# Interrupter.net
KiCad netlist of a schematic drawn in Altium Designer
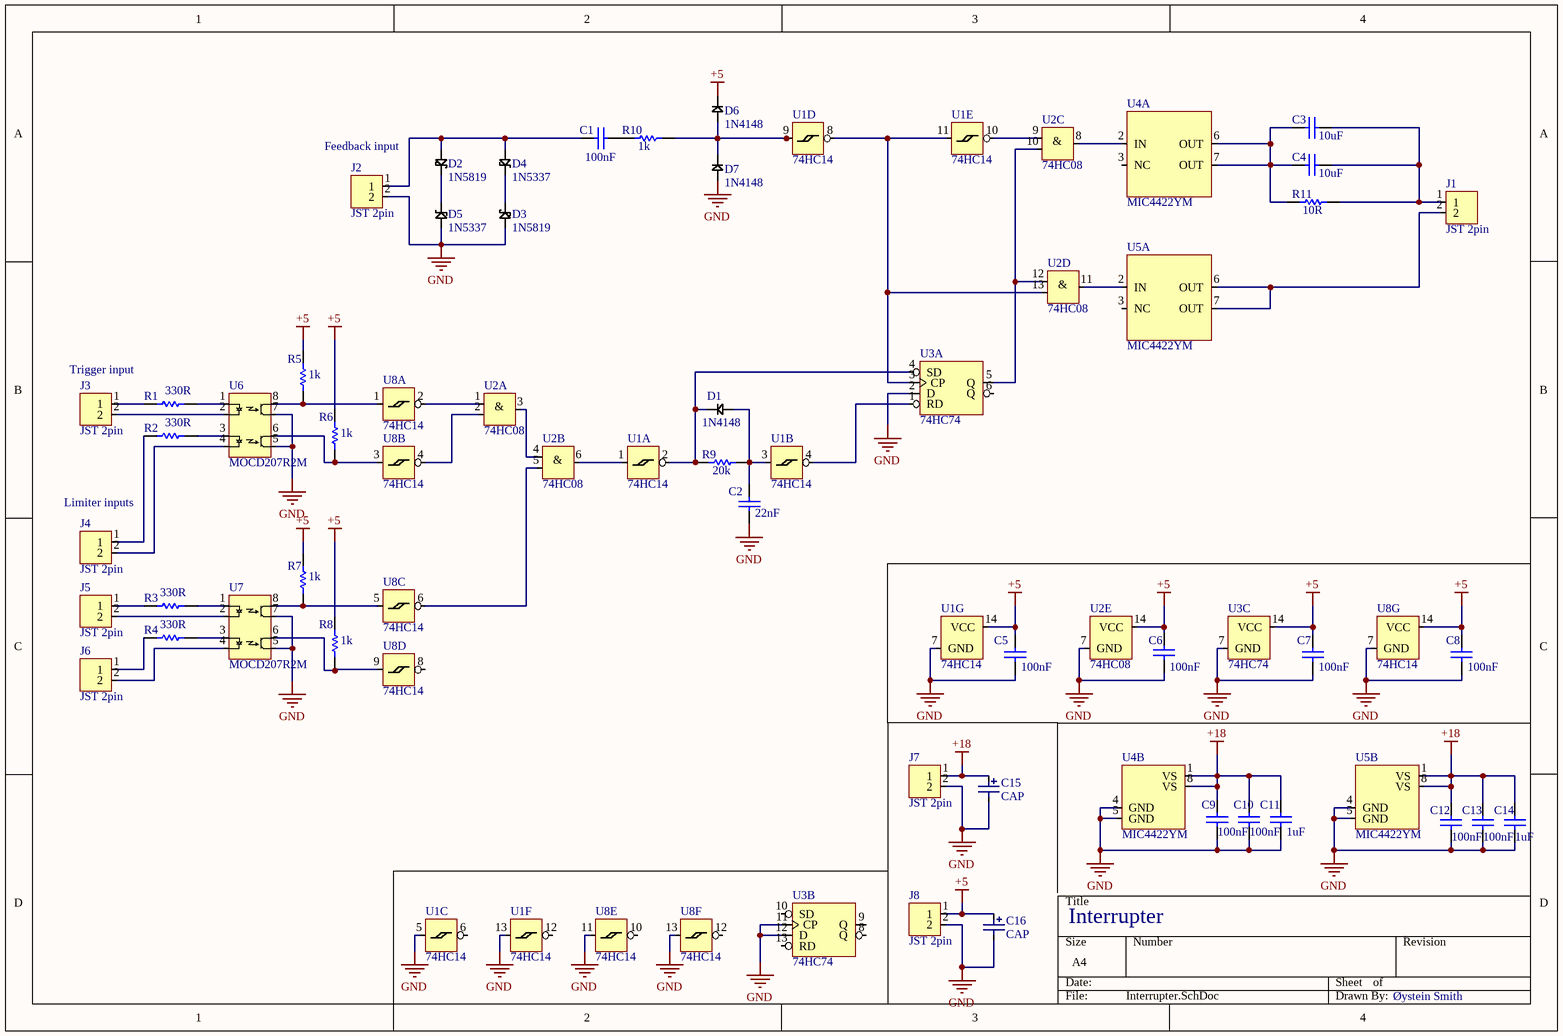
[diagram p0: Interrupter.SchDoc]

(export (version "E")
  (design (tool "Eeschema 10.0.6"))
  (components
    (comp (ref "C1")
      (value "100nF")
      (footprint "CAPC0805(2012)145_L")
      (description "CAP 100nF 25V ±10% 0805 (2012 Metric) Thickness 1.45mm SMD")
      (fields (field (name "TOLERANCE") "±10%") (field (name "Comment") "CAP 100nF 25V 0805(2012)"))
      (libsource (lib "Altium Content Vault") (part "CMP-1036-04410-1"))
    )
    (comp (ref "C2")
      (value "22nF")
      (footprint "CAPC0805(2012)145_L")
      (description "CAP 22nF 25V ±5% 0805 (2012 Metric) Thickness 1.45mm SMD")
      (fields (field (name "TOLERANCE") "±5%") (field (name "Comment") "CAP 22nF 25V 0805(2012)"))
      (libsource (lib "Altium Content Vault") (part "CMP-1036-04050-1"))
    )
    (comp (ref "C3")
      (value "10uF")
      (footprint "CAPC1206(3216)190_L")
      (description "CAP 10uF 25V ±10% 1206 (3216 Metric) Thickness 1.9mm SMD")
      (fields (field (name "TOLERANCE") "±10%") (field (name "Comment") "CAP 10uF 25V 1206(3216)"))
      (libsource (lib "Altium Content Vault") (part "CMP-1037-04979-1"))
    )
    (comp (ref "C4")
      (value "10uF")
      (footprint "CAPC1206(3216)190_L")
      (description "CAP 10uF 25V ±10% 1206 (3216 Metric) Thickness 1.9mm SMD")
      (fields (field (name "TOLERANCE") "±10%") (field (name "Comment") "CAP 10uF 25V 1206(3216)"))
      (libsource (lib "Altium Content Vault") (part "CMP-1037-04979-1"))
    )
    (comp (ref "C5")
      (value "100nF")
      (footprint "CAPC0805(2012)145_M")
      (description "CAP 100nF 25V ±5% 0805 (2012 Metric) Thickness 1.45mm SMD")
      (fields (field (name "TOLERANCE") "±5%") (field (name "Comment") "CAP 100nF 25V 0805(2012)"))
      (libsource (lib "Altium Content Vault") (part "CMP-1036-04408-1"))
    )
    (comp (ref "C6")
      (value "100nF")
      (footprint "CAPC0805(2012)145_M")
      (description "CAP 100nF 25V ±5% 0805 (2012 Metric) Thickness 1.45mm SMD")
      (fields (field (name "TOLERANCE") "±5%") (field (name "Comment") "CAP 100nF 25V 0805(2012)"))
      (libsource (lib "Altium Content Vault") (part "CMP-1036-04408-1"))
    )
    (comp (ref "C7")
      (value "100nF")
      (footprint "CAPC0805(2012)145_M")
      (description "CAP 100nF 25V ±5% 0805 (2012 Metric) Thickness 1.45mm SMD")
      (fields (field (name "TOLERANCE") "±5%") (field (name "Comment") "CAP 100nF 25V 0805(2012)"))
      (libsource (lib "Altium Content Vault") (part "CMP-1036-04408-1"))
    )
    (comp (ref "C8")
      (value "100nF")
      (footprint "CAPC0805(2012)145_M")
      (description "CAP 100nF 25V ±5% 0805 (2012 Metric) Thickness 1.45mm SMD")
      (fields (field (name "TOLERANCE") "±5%") (field (name "Comment") "CAP 100nF 25V 0805(2012)"))
      (libsource (lib "Altium Content Vault") (part "CMP-1036-04408-1"))
    )
    (comp (ref "C9")
      (value "100nF")
      (footprint "CAPC0805(2012)145_M")
      (description "CAP 100nF 25V ±5% 0805 (2012 Metric) Thickness 1.45mm SMD")
      (fields (field (name "TOLERANCE") "±5%") (field (name "Comment") "CAP 100nF 25V 0805(2012)"))
      (libsource (lib "Altium Content Vault") (part "CMP-1036-04408-1"))
    )
    (comp (ref "C10")
      (value "100nF")
      (footprint "CAPC0805(2012)145_M")
      (description "CAP 100nF 25V ±5% 0805 (2012 Metric) Thickness 1.45mm SMD")
      (fields (field (name "TOLERANCE") "±5%") (field (name "Comment") "CAP 100nF 25V 0805(2012)"))
      (libsource (lib "Altium Content Vault") (part "CMP-1036-04408-1"))
    )
    (comp (ref "C11")
      (value "1uF")
      (footprint "CAPC0805(2012)145_N")
      (description "CAP 1uF 25V ±5% 0805 (2012 Metric) Thickness 1.45mm SMD")
      (fields (field (name "TOLERANCE") "±5%") (field (name "Comment") "CAP 1uF 25V 0805(2012)"))
      (libsource (lib "Altium Content Vault") (part "CMP-1036-04752-1"))
    )
    (comp (ref "C12")
      (value "100nF")
      (footprint "CAPC0805(2012)145_M")
      (description "CAP 100nF 25V ±5% 0805 (2012 Metric) Thickness 1.45mm SMD")
      (fields (field (name "TOLERANCE") "±5%") (field (name "Comment") "CAP 100nF 25V 0805(2012)"))
      (libsource (lib "Altium Content Vault") (part "CMP-1036-04408-1"))
    )
    (comp (ref "C13")
      (value "100nF")
      (footprint "CAPC0805(2012)145_M")
      (description "CAP 100nF 25V ±5% 0805 (2012 Metric) Thickness 1.45mm SMD")
      (fields (field (name "TOLERANCE") "±5%") (field (name "Comment") "CAP 100nF 25V 0805(2012)"))
      (libsource (lib "Altium Content Vault") (part "CMP-1036-04408-1"))
    )
    (comp (ref "C14")
      (value "1uF")
      (footprint "CAPC0805(2012)145_N")
      (description "CAP 1uF 25V ±5% 0805 (2012 Metric) Thickness 1.45mm SMD")
      (fields (field (name "TOLERANCE") "±5%") (field (name "Comment") "CAP 1uF 25V 0805(2012)"))
      (libsource (lib "Altium Content Vault") (part "CMP-1036-04752-1"))
    )
    (comp (ref "C15") (value "CAP") (footprint "CAP 2.5mm") (libsource (lib "Schlib1") (part "CAP")))
    (comp (ref "C16") (value "CAP") (footprint "CAP 2.5mm") (libsource (lib "Schlib1") (part "CAP")))
    (comp (ref "D1") (value "1N4148") (footprint "1N4148") (libsource (lib "Schlib1") (part "1N4148")))
    (comp (ref "D2") (value "1N5819") (footprint "1N5819") (libsource (lib "Schlib1") (part "1N5819")))
    (comp (ref "D3") (value "1N5819") (footprint "1N5819") (libsource (lib "Schlib1") (part "1N5819")))
    (comp (ref "D4") (value "1N5337") (footprint "1N5337") (libsource (lib "Schlib1") (part "1N5337")))
    (comp (ref "D5") (value "1N5337") (footprint "1N5337") (libsource (lib "Schlib1") (part "1N5337")))
    (comp (ref "D6") (value "1N4148") (footprint "1N4148") (libsource (lib "Schlib1") (part "1N4148")))
    (comp (ref "D7") (value "1N4148") (footprint "1N4148") (libsource (lib "Schlib1") (part "1N4148")))
    (comp (ref "J1") (value "JST 2pin") (footprint "JST 2pin") (libsource (lib "") (part "JST 2pin_1")))
    (comp (ref "J2") (value "JST 2pin") (footprint "JST 2pin") (libsource (lib "Schlib1") (part "JST 2pin")))
    (comp (ref "J3") (value "JST 2pin") (footprint "JST 2pin") (libsource (lib "Schlib1") (part "JST 2pin")))
    (comp (ref "J4") (value "JST 2pin") (footprint "JST 2pin") (libsource (lib "Schlib1") (part "JST 2pin")))
    (comp (ref "J5") (value "JST 2pin") (footprint "JST 2pin") (libsource (lib "Schlib1") (part "JST 2pin")))
    (comp (ref "J6") (value "JST 2pin") (footprint "JST 2pin") (libsource (lib "Schlib1") (part "JST 2pin")))
    (comp (ref "J7") (value "JST 2pin") (footprint "JST 2pin") (libsource (lib "Schlib1") (part "JST 2pin")))
    (comp (ref "J8") (value "JST 2pin") (footprint "JST 2pin") (libsource (lib "Schlib1") (part "JST 2pin")))
    (comp (ref "R1")
      (value "330R")
      (footprint "RESC0805(2012)_L")
      (description "330R 0.125W 5% 0805 (2012 Metric)  SMD")
      (fields (field (name "TOLERANCE") "5 %") (field (name "POWER") "0.125 W"))
      (libsource (lib "Altium Content Vault") (part "CMP-1013-00062-1"))
    )
    (comp (ref "R2")
      (value "330R")
      (footprint "RESC0805(2012)_L")
      (description "330R 0.125W 5% 0805 (2012 Metric)  SMD")
      (fields (field (name "TOLERANCE") "5 %") (field (name "POWER") "0.125 W"))
      (libsource (lib "Altium Content Vault") (part "CMP-1013-00062-1"))
    )
    (comp (ref "R3")
      (value "330R")
      (footprint "RESC0805(2012)_L")
      (description "330R 0.125W 5% 0805 (2012 Metric)  SMD")
      (fields (field (name "TOLERANCE") "5 %") (field (name "POWER") "0.125 W"))
      (libsource (lib "Altium Content Vault") (part "CMP-1013-00062-1"))
    )
    (comp (ref "R4")
      (value "330R")
      (footprint "RESC0805(2012)_L")
      (description "330R 0.125W 5% 0805 (2012 Metric)  SMD")
      (fields (field (name "TOLERANCE") "5 %") (field (name "POWER") "0.125 W"))
      (libsource (lib "Altium Content Vault") (part "CMP-1013-00062-1"))
    )
    (comp (ref "R5")
      (value "1k")
      (footprint "RESC0805(2012)_N")
      (description "1K 0.125W 5% 0805 (2012 Metric)  SMD")
      (fields (field (name "POWER") "0.125 W") (field (name "TOLERANCE") "5 %"))
      (libsource (lib "Altium Content Vault") (part "CMP-1013-00074-1"))
    )
    (comp (ref "R6")
      (value "1k")
      (footprint "RESC0805(2012)_N")
      (description "1K 0.125W 5% 0805 (2012 Metric)  SMD")
      (fields (field (name "POWER") "0.125 W") (field (name "TOLERANCE") "5 %"))
      (libsource (lib "Altium Content Vault") (part "CMP-1013-00074-1"))
    )
    (comp (ref "R7")
      (value "1k")
      (footprint "RESC0805(2012)_N")
      (description "1K 0.125W 5% 0805 (2012 Metric)  SMD")
      (fields (field (name "POWER") "0.125 W") (field (name "TOLERANCE") "5 %"))
      (libsource (lib "Altium Content Vault") (part "CMP-1013-00074-1"))
    )
    (comp (ref "R8")
      (value "1k")
      (footprint "RESC0805(2012)_N")
      (description "1K 0.125W 5% 0805 (2012 Metric)  SMD")
      (fields (field (name "POWER") "0.125 W") (field (name "TOLERANCE") "5 %"))
      (libsource (lib "Altium Content Vault") (part "CMP-1013-00074-1"))
    )
    (comp (ref "R9")
      (value "20k")
      (footprint "RESC0805(2012)_N")
      (description "20K 0.125W 1% 0805 (2012 Metric)  SMD")
      (fields (field (name "POWER") "0.125 W") (field (name "TOLERANCE") "1 %"))
      (libsource (lib "Altium Content Vault") (part "CMP-1013-00655-1"))
    )
    (comp (ref "R10")
      (value "1k")
      (footprint "RESC0805(2012)_M")
      (description "1K 0.125W 1% 0805 (2012 Metric)  SMD")
      (fields (field (name "TOLERANCE") "1 %") (field (name "POWER") "0.125 W"))
      (libsource (lib "Altium Content Vault") (part "CMP-1013-00510-1"))
    )
    (comp (ref "R11")
      (value "10R")
      (footprint "RESC0805(2012)_L")
      (description "10R 0.125W 5% 0805 (2012 Metric)  SMD")
      (fields (field (name "POWER") "0.125 W") (field (name "TOLERANCE") "5 %"))
      (libsource (lib "Altium Content Vault") (part "CMP-1013-00026-1"))
    )
    (comp (ref "U1") (value "74HC14") (footprint "SOP14") (libsource (lib "Schlib1") (part "74HC14")))
    (comp (ref "U2") (value "74HC08") (footprint "SOP14") (libsource (lib "Schlib1") (part "74HC08")))
    (comp (ref "U3") (value "74HC74") (footprint "SOP14") (libsource (lib "Schlib1") (part "74HC74")))
    (comp (ref "U4") (value "MIC4422YM") (footprint "SOP8") (libsource (lib "Schlib1") (part "MIC4422YM")))
    (comp (ref "U5") (value "MIC4422YM") (footprint "SOP8") (libsource (lib "Schlib1") (part "MIC4422YM")))
    (comp (ref "U6") (value "MOCD207R2M") (footprint "SOP8") (libsource (lib "Schlib1") (part "MOCD207R2M")))
    (comp (ref "U7") (value "MOCD207R2M") (footprint "SOP8") (libsource (lib "Schlib1") (part "MOCD207R2M")))
    (comp (ref "U8") (value "74HC14") (footprint "SOP14") (libsource (lib "Schlib1") (part "74HC14")))
  )
  (nets
    (net (code "1") (name "+5") (class "Default")
      (node (ref "C16") (pin "2") (pinfunction "2_2") (pintype "passive"))
      (node (ref "C5") (pin "2") (pinfunction "2_2") (pintype "passive"))
      (node (ref "C6") (pin "2") (pinfunction "2_2") (pintype "passive"))
      (node (ref "C7") (pin "2") (pinfunction "2_2") (pintype "passive"))
      (node (ref "C8") (pin "2") (pinfunction "2_2") (pintype "passive"))
      (node (ref "D6") (pin "K") (pinfunction "K_K") (pintype "passive"))
      (node (ref "J8") (pin "1") (pinfunction "1_1") (pintype "passive"))
      (node (ref "R5") (pin "2") (pinfunction "2_2") (pintype "passive"))
      (node (ref "R6") (pin "2") (pinfunction "2_2") (pintype "passive"))
      (node (ref "R7") (pin "2") (pinfunction "2_2") (pintype "passive"))
      (node (ref "R8") (pin "2") (pinfunction "2_2") (pintype "passive"))
      (node (ref "U1") (pin "14") (pinfunction "VCC_14") (pintype "passive"))
      (node (ref "U2") (pin "14") (pinfunction "VCC_14") (pintype "passive"))
      (node (ref "U3") (pin "14") (pinfunction "VCC_14") (pintype "passive"))
      (node (ref "U8") (pin "14") (pinfunction "VCC_14") (pintype "passive"))
    )
    (net (code "2") (name "+18") (class "Default")
      (node (ref "C10") (pin "2") (pinfunction "2_2") (pintype "passive"))
      (node (ref "C11") (pin "2") (pinfunction "2_2") (pintype "passive"))
      (node (ref "C12") (pin "2") (pinfunction "2_2") (pintype "passive"))
      (node (ref "C13") (pin "2") (pinfunction "2_2") (pintype "passive"))
      (node (ref "C14") (pin "2") (pinfunction "2_2") (pintype "passive"))
      (node (ref "C15") (pin "2") (pinfunction "2_2") (pintype "passive"))
      (node (ref "C9") (pin "2") (pinfunction "2_2") (pintype "passive"))
      (node (ref "J7") (pin "1") (pinfunction "1_1") (pintype "passive"))
      (node (ref "U4") (pin "1") (pinfunction "VS_1") (pintype "passive"))
      (node (ref "U4") (pin "8") (pinfunction "VS_8") (pintype "passive"))
      (node (ref "U5") (pin "1") (pinfunction "VS_1") (pintype "passive"))
      (node (ref "U5") (pin "8") (pinfunction "VS_8") (pintype "passive"))
    )
    (net (code "3") (name "GND") (class "Default")
      (node (ref "C10") (pin "1") (pinfunction "1_1") (pintype "passive"))
      (node (ref "C11") (pin "1") (pinfunction "1_1") (pintype "passive"))
      (node (ref "C12") (pin "1") (pinfunction "1_1") (pintype "passive"))
      (node (ref "C13") (pin "1") (pinfunction "1_1") (pintype "passive"))
      (node (ref "C14") (pin "1") (pinfunction "1_1") (pintype "passive"))
      (node (ref "C15") (pin "1") (pinfunction "1_1") (pintype "passive"))
      (node (ref "C16") (pin "1") (pinfunction "1_1") (pintype "passive"))
      (node (ref "C2") (pin "1") (pinfunction "1_1") (pintype "passive"))
      (node (ref "C5") (pin "1") (pinfunction "1_1") (pintype "passive"))
      (node (ref "C6") (pin "1") (pinfunction "1_1") (pintype "passive"))
      (node (ref "C7") (pin "1") (pinfunction "1_1") (pintype "passive"))
      (node (ref "C8") (pin "1") (pinfunction "1_1") (pintype "passive"))
      (node (ref "C9") (pin "1") (pinfunction "1_1") (pintype "passive"))
      (node (ref "D3") (pin "A") (pinfunction "A_A") (pintype "passive"))
      (node (ref "D5") (pin "A") (pinfunction "A_A") (pintype "passive"))
      (node (ref "D7") (pin "A") (pinfunction "A_A") (pintype "passive"))
      (node (ref "J2") (pin "2") (pinfunction "2_2") (pintype "passive"))
      (node (ref "J7") (pin "2") (pinfunction "2_2") (pintype "passive"))
      (node (ref "J8") (pin "2") (pinfunction "2_2") (pintype "passive"))
      (node (ref "U1") (pin "13") (pinfunction "13_13") (pintype "passive"))
      (node (ref "U1") (pin "5") (pinfunction "5_5") (pintype "passive"))
      (node (ref "U1") (pin "7") (pinfunction "GND_7") (pintype "passive"))
      (node (ref "U2") (pin "7") (pinfunction "GND_7") (pintype "passive"))
      (node (ref "U3") (pin "11") (pinfunction "CP_11") (pintype "passive"))
      (node (ref "U3") (pin "12") (pinfunction "D_12") (pintype "passive"))
      (node (ref "U3") (pin "2") (pinfunction "D_2") (pintype "passive"))
      (node (ref "U3") (pin "7") (pinfunction "GND_7") (pintype "passive"))
      (node (ref "U4") (pin "4") (pinfunction "GND_4") (pintype "passive"))
      (node (ref "U4") (pin "5") (pinfunction "GND_5") (pintype "passive"))
      (node (ref "U5") (pin "4") (pinfunction "GND_4") (pintype "passive"))
      (node (ref "U5") (pin "5") (pinfunction "GND_5") (pintype "passive"))
      (node (ref "U6") (pin "5") (pinfunction "5_5") (pintype "passive"))
      (node (ref "U6") (pin "7") (pinfunction "7_7") (pintype "passive"))
      (node (ref "U7") (pin "5") (pinfunction "5_5") (pintype "passive"))
      (node (ref "U7") (pin "7") (pinfunction "7_7") (pintype "passive"))
      (node (ref "U8") (pin "11") (pinfunction "11_11") (pintype "passive"))
      (node (ref "U8") (pin "13") (pinfunction "13_13") (pintype "passive"))
      (node (ref "U8") (pin "7") (pinfunction "GND_7") (pintype "passive"))
    )
    (net (code "4") (name "Net-(C1-Pad1)") (class "Default")
      (node (ref "C1") (pin "1") (pinfunction "1_1") (pintype "passive"))
      (node (ref "D2") (pin "A") (pinfunction "A_A") (pintype "passive"))
      (node (ref "D4") (pin "A") (pinfunction "A_A") (pintype "passive"))
      (node (ref "J2") (pin "1") (pinfunction "1_1") (pintype "passive"))
    )
    (net (code "5") (name "Net-(C1-Pad2)") (class "Default")
      (node (ref "C1") (pin "2") (pinfunction "2_2") (pintype "passive"))
      (node (ref "R10") (pin "1") (pinfunction "1_1") (pintype "passive"))
    )
    (net (code "6") (name "Net-(C2-Pad2)") (class "Default")
      (node (ref "C2") (pin "2") (pinfunction "2_2") (pintype "passive"))
      (node (ref "D1") (pin "A") (pinfunction "A_A") (pintype "passive"))
      (node (ref "R9") (pin "2") (pinfunction "2_2") (pintype "passive"))
      (node (ref "U1") (pin "3") (pinfunction "3_3") (pintype "passive"))
    )
    (net (code "7") (name "Net-(C3-Pad1)") (class "Default")
      (node (ref "C3") (pin "1") (pinfunction "1_1") (pintype "passive"))
      (node (ref "C4") (pin "1") (pinfunction "1_1") (pintype "passive"))
      (node (ref "R11") (pin "1") (pinfunction "1_1") (pintype "passive"))
      (node (ref "U4") (pin "6") (pinfunction "OUT_6") (pintype "passive"))
      (node (ref "U4") (pin "7") (pinfunction "OUT_7") (pintype "passive"))
    )
    (net (code "8") (name "Net-(C3-Pad2)") (class "Default")
      (node (ref "C3") (pin "2") (pinfunction "2_2") (pintype "passive"))
      (node (ref "C4") (pin "2") (pinfunction "2_2") (pintype "passive"))
      (node (ref "J1") (pin "1") (pinfunction "1_1") (pintype "passive"))
      (node (ref "R11") (pin "2") (pinfunction "2_2") (pintype "passive"))
    )
    (net (code "9") (name "Net-(D2-PadK)") (class "Default")
      (node (ref "D2") (pin "K") (pinfunction "K_K") (pintype "passive"))
      (node (ref "D5") (pin "K") (pinfunction "K_K") (pintype "passive"))
    )
    (net (code "10") (name "Net-(D3-PadK)") (class "Default")
      (node (ref "D3") (pin "K") (pinfunction "K_K") (pintype "passive"))
      (node (ref "D4") (pin "K") (pinfunction "K_K") (pintype "passive"))
    )
    (net (code "11") (name "Net-(D6-PadA)") (class "Default")
      (node (ref "D6") (pin "A") (pinfunction "A_A") (pintype "passive"))
      (node (ref "D7") (pin "K") (pinfunction "K_K") (pintype "passive"))
      (node (ref "R10") (pin "2") (pinfunction "2_2") (pintype "passive"))
      (node (ref "U1") (pin "9") (pinfunction "9_9") (pintype "passive"))
    )
    (net (code "12") (name "Net-(J1-Pad2)") (class "Default")
      (node (ref "J1") (pin "2") (pinfunction "2_2") (pintype "passive"))
      (node (ref "U5") (pin "6") (pinfunction "OUT_6") (pintype "passive"))
      (node (ref "U5") (pin "7") (pinfunction "OUT_7") (pintype "passive"))
    )
    (net (code "13") (name "Net-(J3-Pad1)") (class "Default")
      (node (ref "J3") (pin "1") (pinfunction "1_1") (pintype "passive"))
      (node (ref "R1") (pin "2") (pinfunction "2_2") (pintype "passive"))
    )
    (net (code "14") (name "Net-(J3-Pad2)") (class "Default")
      (node (ref "J3") (pin "2") (pinfunction "2_2") (pintype "passive"))
      (node (ref "U6") (pin "2") (pinfunction "2_2") (pintype "passive"))
    )
    (net (code "15") (name "Net-(J4-Pad1)") (class "Default")
      (node (ref "J4") (pin "1") (pinfunction "1_1") (pintype "passive"))
      (node (ref "R2") (pin "2") (pinfunction "2_2") (pintype "passive"))
    )
    (net (code "16") (name "Net-(J4-Pad2)") (class "Default")
      (node (ref "J4") (pin "2") (pinfunction "2_2") (pintype "passive"))
      (node (ref "U6") (pin "4") (pinfunction "4_4") (pintype "passive"))
    )
    (net (code "17") (name "Net-(J5-Pad1)") (class "Default")
      (node (ref "J5") (pin "1") (pinfunction "1_1") (pintype "passive"))
      (node (ref "R3") (pin "2") (pinfunction "2_2") (pintype "passive"))
    )
    (net (code "18") (name "Net-(J5-Pad2)") (class "Default")
      (node (ref "J5") (pin "2") (pinfunction "2_2") (pintype "passive"))
      (node (ref "U7") (pin "2") (pinfunction "2_2") (pintype "passive"))
    )
    (net (code "19") (name "Net-(J6-Pad1)") (class "Default")
      (node (ref "J6") (pin "1") (pinfunction "1_1") (pintype "passive"))
      (node (ref "R4") (pin "2") (pinfunction "2_2") (pintype "passive"))
    )
    (net (code "20") (name "Net-(J6-Pad2)") (class "Default")
      (node (ref "J6") (pin "2") (pinfunction "2_2") (pintype "passive"))
      (node (ref "U7") (pin "4") (pinfunction "4_4") (pintype "passive"))
    )
    (net (code "21") (name "Net-(R1-Pad1)") (class "Default")
      (node (ref "R1") (pin "1") (pinfunction "1_1") (pintype "passive"))
      (node (ref "U6") (pin "1") (pinfunction "1_1") (pintype "passive"))
    )
    (net (code "22") (name "Net-(R2-Pad1)") (class "Default")
      (node (ref "R2") (pin "1") (pinfunction "1_1") (pintype "passive"))
      (node (ref "U6") (pin "3") (pinfunction "3_3") (pintype "passive"))
    )
    (net (code "23") (name "Net-(R3-Pad1)") (class "Default")
      (node (ref "R3") (pin "1") (pinfunction "1_1") (pintype "passive"))
      (node (ref "U7") (pin "1") (pinfunction "1_1") (pintype "passive"))
    )
    (net (code "24") (name "Net-(R4-Pad1)") (class "Default")
      (node (ref "R4") (pin "1") (pinfunction "1_1") (pintype "passive"))
      (node (ref "U7") (pin "3") (pinfunction "3_3") (pintype "passive"))
    )
    (net (code "25") (name "Net-(R5-Pad1)") (class "Default")
      (node (ref "R5") (pin "1") (pinfunction "1_1") (pintype "passive"))
      (node (ref "U6") (pin "8") (pinfunction "8_8") (pintype "passive"))
      (node (ref "U8") (pin "1") (pinfunction "1_1") (pintype "passive"))
    )
    (net (code "26") (name "Net-(R6-Pad1)") (class "Default")
      (node (ref "R6") (pin "1") (pinfunction "1_1") (pintype "passive"))
      (node (ref "U6") (pin "6") (pinfunction "6_6") (pintype "passive"))
      (node (ref "U8") (pin "3") (pinfunction "3_3") (pintype "passive"))
    )
    (net (code "27") (name "Net-(R7-Pad1)") (class "Default")
      (node (ref "R7") (pin "1") (pinfunction "1_1") (pintype "passive"))
      (node (ref "U7") (pin "8") (pinfunction "8_8") (pintype "passive"))
      (node (ref "U8") (pin "5") (pinfunction "5_5") (pintype "passive"))
    )
    (net (code "28") (name "Net-(R8-Pad1)") (class "Default")
      (node (ref "R8") (pin "1") (pinfunction "1_1") (pintype "passive"))
      (node (ref "U7") (pin "6") (pinfunction "6_6") (pintype "passive"))
      (node (ref "U8") (pin "9") (pinfunction "9_9") (pintype "passive"))
    )
    (net (code "29") (name "Net-(U1-Pad1)") (class "Default")
      (node (ref "U1") (pin "1") (pinfunction "1_1") (pintype "passive"))
      (node (ref "U2") (pin "6") (pinfunction "6_6") (pintype "passive"))
    )
    (net (code "30") (name "Net-(U1-Pad10)") (class "Default")
      (node (ref "U1") (pin "10") (pinfunction "10_10") (pintype "passive"))
      (node (ref "U2") (pin "9") (pinfunction "9_9") (pintype "passive"))
    )
    (net (code "31") (name "Net-(U2-Pad1)") (class "Default")
      (node (ref "U2") (pin "1") (pinfunction "1_1") (pintype "passive"))
      (node (ref "U8") (pin "2") (pinfunction "2_2") (pintype "passive"))
    )
    (net (code "32") (name "Net-(U2-Pad2)") (class "Default")
      (node (ref "U2") (pin "2") (pinfunction "2_2") (pintype "passive"))
      (node (ref "U8") (pin "4") (pinfunction "4_4") (pintype "passive"))
    )
    (net (code "33") (name "Net-(U2-Pad3)") (class "Default")
      (node (ref "U2") (pin "3") (pinfunction "3_3") (pintype "passive"))
      (node (ref "U2") (pin "4") (pinfunction "4_4") (pintype "passive"))
    )
    (net (code "34") (name "Net-(U2-Pad5)") (class "Default")
      (node (ref "U2") (pin "5") (pinfunction "5_5") (pintype "passive"))
      (node (ref "U8") (pin "6") (pinfunction "6_6") (pintype "passive"))
    )
    (net (code "35") (name "Net-(U2-Pad10)") (class "Default")
      (node (ref "U2") (pin "10") (pinfunction "10_10") (pintype "passive"))
      (node (ref "U2") (pin "12") (pinfunction "12_12") (pintype "passive"))
      (node (ref "U3") (pin "5") (pinfunction "Q_5") (pintype "passive"))
    )
    (net (code "36") (name "Net-(U3A-CP)") (class "Default")
      (node (ref "U1") (pin "11") (pinfunction "11_11") (pintype "passive"))
      (node (ref "U1") (pin "8") (pinfunction "8_8") (pintype "passive"))
      (node (ref "U2") (pin "13") (pinfunction "13_13") (pintype "passive"))
      (node (ref "U3") (pin "3") (pinfunction "CP_3") (pintype "passive"))
    )
    (net (code "37") (name "Net-(U3A-RD)") (class "Default")
      (node (ref "U1") (pin "4") (pinfunction "4_4") (pintype "passive"))
      (node (ref "U3") (pin "1") (pinfunction "RD_1") (pintype "passive"))
    )
    (net (code "38") (name "Net-(U3A-SD)") (class "Default")
      (node (ref "D1") (pin "K") (pinfunction "K_K") (pintype "passive"))
      (node (ref "R9") (pin "1") (pinfunction "1_1") (pintype "passive"))
      (node (ref "U1") (pin "2") (pinfunction "2_2") (pintype "passive"))
      (node (ref "U3") (pin "4") (pinfunction "SD_4") (pintype "passive"))
    )
    (net (code "39") (name "Net-(U4A-IN)") (class "Default")
      (node (ref "U2") (pin "8") (pinfunction "8_8") (pintype "passive"))
      (node (ref "U4") (pin "2") (pinfunction "IN_2") (pintype "passive"))
    )
    (net (code "40") (name "Net-(U5A-IN)") (class "Default")
      (node (ref "U2") (pin "11") (pinfunction "11_11") (pintype "passive"))
      (node (ref "U5") (pin "2") (pinfunction "IN_2") (pintype "passive"))
    )
    (net (code "41") (name "unconnected-(U1-Pad6)") (class "Default")
      (node (ref "U1") (pin "6") (pinfunction "6_6") (pintype "passive"))
    )
    (net (code "42") (name "unconnected-(U1-Pad12)") (class "Default")
      (node (ref "U1") (pin "12") (pinfunction "12_12") (pintype "passive"))
    )
    (net (code "43") (name "unconnected-(U3A-Q-Pad6)") (class "Default")
      (node (ref "U3") (pin "6") (pinfunction "Q_6") (pintype "passive"))
    )
    (net (code "44") (name "unconnected-(U3B-Q-Pad8)") (class "Default")
      (node (ref "U3") (pin "8") (pinfunction "Q_8") (pintype "passive"))
    )
    (net (code "45") (name "unconnected-(U3B-Q-Pad9)") (class "Default")
      (node (ref "U3") (pin "9") (pinfunction "Q_9") (pintype "passive"))
    )
    (net (code "46") (name "unconnected-(U3B-RD-Pad13)") (class "Default")
      (node (ref "U3") (pin "13") (pinfunction "RD_13") (pintype "passive"))
    )
    (net (code "47") (name "unconnected-(U3B-SD-Pad10)") (class "Default")
      (node (ref "U3") (pin "10") (pinfunction "SD_10") (pintype "passive"))
    )
    (net (code "48") (name "unconnected-(U4A-NC-Pad3)") (class "Default")
      (node (ref "U4") (pin "3") (pinfunction "NC_3") (pintype "passive"))
    )
    (net (code "49") (name "unconnected-(U5A-NC-Pad3)") (class "Default")
      (node (ref "U5") (pin "3") (pinfunction "NC_3") (pintype "passive"))
    )
    (net (code "50") (name "unconnected-(U8-Pad8)") (class "Default")
      (node (ref "U8") (pin "8") (pinfunction "8_8") (pintype "passive"))
    )
    (net (code "51") (name "unconnected-(U8-Pad10)") (class "Default")
      (node (ref "U8") (pin "10") (pinfunction "10_10") (pintype "passive"))
    )
    (net (code "52") (name "unconnected-(U8-Pad12)") (class "Default")
      (node (ref "U8") (pin "12") (pinfunction "12_12") (pintype "passive"))
    )
  )
)
